# RP2040_MCU.net
KiCad netlist of a schematic drawn in Altium Designer
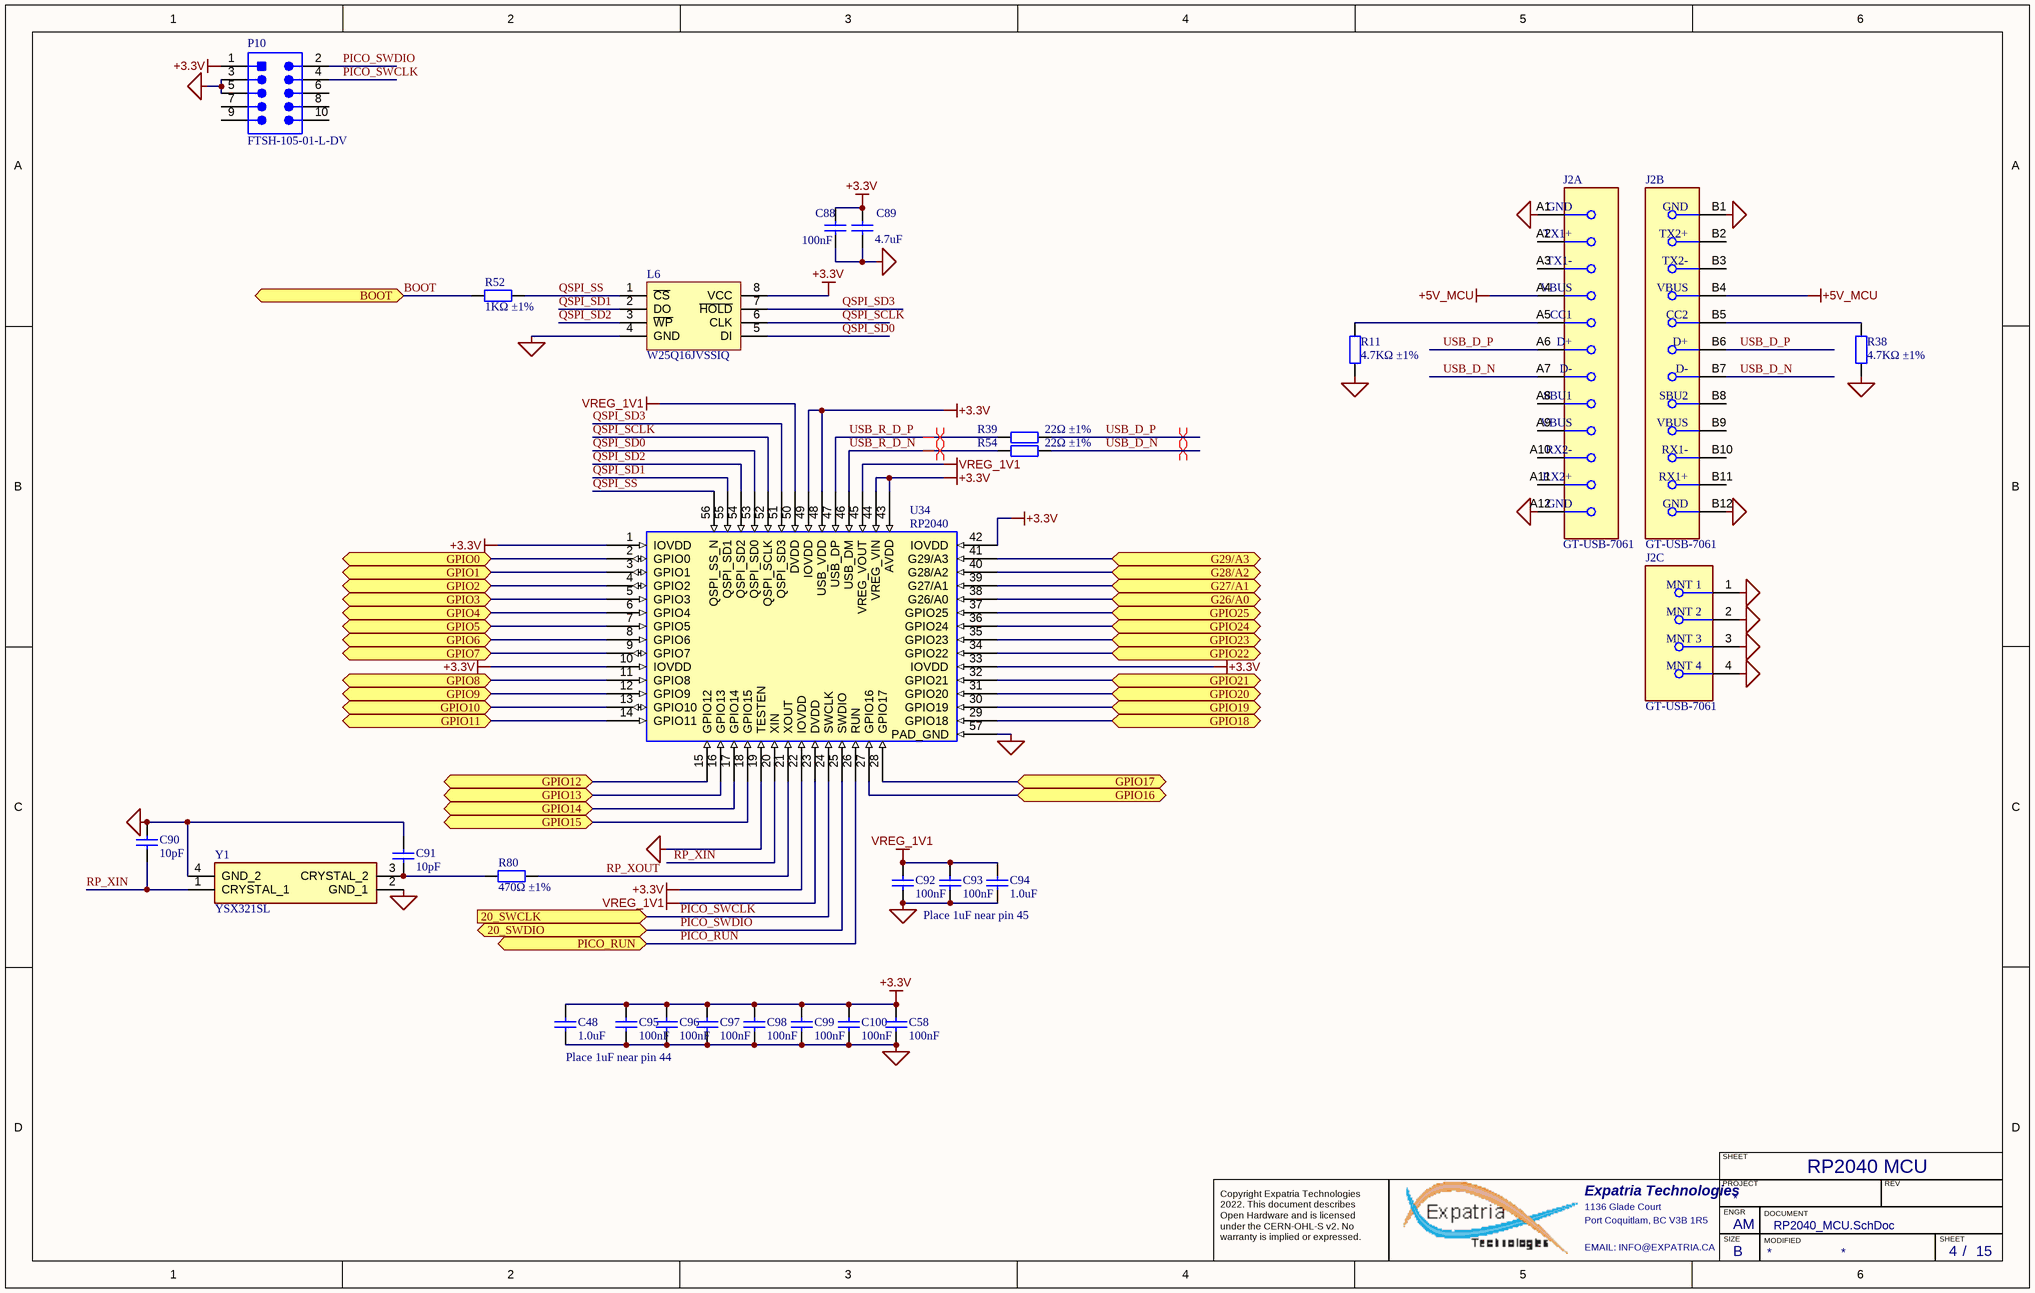
[diagram p0: RP2040_MCU.SchDoc]

(export (version "E")
  (design (tool "Eeschema 10.0.6"))
  (components
    (comp (ref "C48")
      (value "1.0uF")
      (footprint "0402_C")
      (description "Chip capacitor")
      (fields
        (field (name "MANUFACTURER") "Samsung Electro-Mechanics")
        (field (name "PARTNUMBER") "CL05A105KA5NQNC")
      )
      (libsource (lib "Cap") (part "0402 1.0uF (105) 10% 25V"))
    )
    (comp (ref "C58")
      (value "100nF")
      (footprint "0402_C")
      (description "Chip capacitors")
      (fields
        (field (name "MANUFACTURER") "Samsung Electro-Mechanics")
        (field (name "PARTNUMBER") "CL05B104KO5NNNC")
      )
      (libsource (lib "Cap") (part "0402 100nF (104) 10% 16V"))
    )
    (comp (ref "C88")
      (value "100nF")
      (footprint "0402_C")
      (description "Chip capacitors")
      (fields
        (field (name "MANUFACTURER") "Samsung Electro-Mechanics")
        (field (name "PARTNUMBER") "CL05B104KO5NNNC")
      )
      (libsource (lib "Cap") (part "0402 100nF (104) 10% 16V"))
    )
    (comp (ref "C89")
      (value "4.7uF")
      (footprint "0402_C")
      (description "Chip capacitor")
      (fields
        (field (name "MANUFACTURER") "Samsung Electro-Mechanics")
        (field (name "PARTNUMBER") "CL05A475MP5NRNC")
      )
      (libsource (lib "Cap") (part "0402 4.7uF (475) 20% 10V"))
    )
    (comp (ref "C90")
      (value "10pF")
      (footprint "0402_C")
      (description "Chip capacitors")
      (fields
        (field (name "MANUFACTURER") "Samsung Electro-Mechanics")
        (field (name "PARTNUMBER") "CL05C100JB5NNNC")
      )
      (libsource (lib "Cap") (part "0402 10pF (100) 5% 50V"))
    )
    (comp (ref "C91")
      (value "10pF")
      (footprint "0402_C")
      (description "Chip capacitors")
      (fields
        (field (name "MANUFACTURER") "Samsung Electro-Mechanics")
        (field (name "PARTNUMBER") "CL05C100JB5NNNC")
      )
      (libsource (lib "Cap") (part "0402 10pF (100) 5% 50V"))
    )
    (comp (ref "C92")
      (value "100nF")
      (footprint "0402_C")
      (description "Chip capacitors")
      (fields
        (field (name "MANUFACTURER") "Samsung Electro-Mechanics")
        (field (name "PARTNUMBER") "CL05B104KO5NNNC")
      )
      (libsource (lib "Cap") (part "0402 100nF (104) 10% 16V"))
    )
    (comp (ref "C93")
      (value "100nF")
      (footprint "0402_C")
      (description "Chip capacitors")
      (fields
        (field (name "MANUFACTURER") "Samsung Electro-Mechanics")
        (field (name "PARTNUMBER") "CL05B104KO5NNNC")
      )
      (libsource (lib "Cap") (part "0402 100nF (104) 10% 16V"))
    )
    (comp (ref "C94")
      (value "1.0uF")
      (footprint "0402_C")
      (description "Chip capacitor")
      (fields
        (field (name "MANUFACTURER") "Samsung Electro-Mechanics")
        (field (name "PARTNUMBER") "CL05A105KA5NQNC")
      )
      (libsource (lib "Cap") (part "0402 1.0uF (105) 10% 25V"))
    )
    (comp (ref "C95")
      (value "100nF")
      (footprint "0402_C")
      (description "Chip capacitors")
      (fields
        (field (name "MANUFACTURER") "Samsung Electro-Mechanics")
        (field (name "PARTNUMBER") "CL05B104KO5NNNC")
      )
      (libsource (lib "Cap") (part "0402 100nF (104) 10% 16V"))
    )
    (comp (ref "C96")
      (value "100nF")
      (footprint "0402_C")
      (description "Chip capacitors")
      (fields
        (field (name "MANUFACTURER") "Samsung Electro-Mechanics")
        (field (name "PARTNUMBER") "CL05B104KO5NNNC")
      )
      (libsource (lib "Cap") (part "0402 100nF (104) 10% 16V"))
    )
    (comp (ref "C97")
      (value "100nF")
      (footprint "0402_C")
      (description "Chip capacitors")
      (fields
        (field (name "MANUFACTURER") "Samsung Electro-Mechanics")
        (field (name "PARTNUMBER") "CL05B104KO5NNNC")
      )
      (libsource (lib "Cap") (part "0402 100nF (104) 10% 16V"))
    )
    (comp (ref "C98")
      (value "100nF")
      (footprint "0402_C")
      (description "Chip capacitors")
      (fields
        (field (name "MANUFACTURER") "Samsung Electro-Mechanics")
        (field (name "PARTNUMBER") "CL05B104KO5NNNC")
      )
      (libsource (lib "Cap") (part "0402 100nF (104) 10% 16V"))
    )
    (comp (ref "C99")
      (value "100nF")
      (footprint "0402_C")
      (description "Chip capacitors")
      (fields
        (field (name "MANUFACTURER") "Samsung Electro-Mechanics")
        (field (name "PARTNUMBER") "CL05B104KO5NNNC")
      )
      (libsource (lib "Cap") (part "0402 100nF (104) 10% 16V"))
    )
    (comp (ref "C100")
      (value "100nF")
      (footprint "0402_C")
      (description "Chip capacitors")
      (fields
        (field (name "MANUFACTURER") "Samsung Electro-Mechanics")
        (field (name "PARTNUMBER") "CL05B104KO5NNNC")
      )
      (libsource (lib "Cap") (part "0402 100nF (104) 10% 16V"))
    )
    (comp (ref "J2")
      (value "GT-USB-7061")
      (footprint "USB-C-SMD_GT-USB-7061")
      (description "CONN RCP USB3.1 TYPEC 24P SMD VERT")
      (fields (field (name "MANUFACTURER") "G-Switch"))
      (libsource (lib "I2C_Jog_Controller") (part "USBC-GT-USB-7061"))
    )
    (comp (ref "L6")
      (value "W25Q16JVSSIQ")
      (footprint "SOIC-8_208mil")
      (description "Flash ROM")
      (libsource (lib "IC") (part "W25Q128JVSIQTR_[C97521]"))
    )
    (comp (ref "P10")
      (value "FTSH-105-01-L-DV")
      (footprint "SMTC-FTSH-105-01-L-DV_V")
      (description "Male Header, Pitch 1.27 mm, 2 x 5 Position, Height 5.96 mm, -55 to 125 degC, RoHS, Bulk")
      (fields (field (name "MANUFACTURER") "Samtec"))
      (libsource (lib "Altium Content Vault") (part "CN-2P-M-R10"))
    )
    (comp (ref "R11")
      (value "4.7KΩ ±1%")
      (footprint "0402_R")
      (description "Chip resistor")
      (fields (field (name "MANUFACTURER") "Uniroyal Elec") (field (name "PARTNUMBER") "0402WGF4701TCE"))
      (libsource (lib "RES") (part "0402 4.7K (4701) 1%"))
    )
    (comp (ref "R38")
      (value "4.7KΩ ±1%")
      (footprint "0402_R")
      (description "Chip resistor")
      (fields (field (name "MANUFACTURER") "Uniroyal Elec") (field (name "PARTNUMBER") "0402WGF4701TCE"))
      (libsource (lib "") (part "0402 4.7K (4701) 1%_1"))
    )
    (comp (ref "R39")
      (value "22Ω ±1%")
      (footprint "0402_R")
      (description "Chip resistor")
      (fields (field (name "MANUFACTURER") "Uniroyal Elec") (field (name "PARTNUMBER") "0402WGF220JTCE"))
      (libsource (lib "RES") (part "0402 22R (22R0) 1%"))
    )
    (comp (ref "R52")
      (value "1KΩ ±1%")
      (footprint "0402_R")
      (description "Chip resistor")
      (fields (field (name "MANUFACTURER") "Uniroyal Elec") (field (name "PARTNUMBER") "0402WGF1001TCE"))
      (libsource (lib "RES") (part "0402 1K (1001) 1%"))
    )
    (comp (ref "R54")
      (value "22Ω ±1%")
      (footprint "0402_R")
      (description "Chip resistor")
      (fields (field (name "MANUFACTURER") "Uniroyal Elec") (field (name "PARTNUMBER") "0402WGF220JTCE"))
      (libsource (lib "RES") (part "0402 22R (22R0) 1%"))
    )
    (comp (ref "R80")
      (value "470Ω ±1%")
      (footprint "0402_R")
      (description "Chip resistor")
      (fields (field (name "MANUFACTURER") "Uniroyal Elec") (field (name "PARTNUMBER") "0402WGF4700TCE"))
      (libsource (lib "RES") (part "0402 470R (4700) 1%"))
    )
    (comp (ref "U34")
      (value "RP2040")
      (footprint "RP2040")
      (description "RP2040 First MCU from RPI")
      (libsource (lib "Universal_CNC_Breakout") (part "RP2040"))
    )
    (comp (ref "Y1")
      (value "YSX321SL")
      (footprint "YSX321SL")
      (description "Crystal or Oscillator")
      (libsource (lib "*") (part "YSX321SL"))
    )
  )
  (nets
    (net (code "1") (name "+3.3V") (class "Default")
      (node (ref "C100") (pin "2") (pinfunction "2_2") (pintype "passive"))
      (node (ref "C48") (pin "2") (pinfunction "2_2") (pintype "passive"))
      (node (ref "C58") (pin "2") (pinfunction "2_2") (pintype "passive"))
      (node (ref "C88") (pin "2") (pinfunction "2_2") (pintype "passive"))
      (node (ref "C89") (pin "2") (pinfunction "2_2") (pintype "passive"))
      (node (ref "C95") (pin "2") (pinfunction "2_2") (pintype "passive"))
      (node (ref "C96") (pin "2") (pinfunction "2_2") (pintype "passive"))
      (node (ref "C97") (pin "2") (pinfunction "2_2") (pintype "passive"))
      (node (ref "C98") (pin "2") (pinfunction "2_2") (pintype "passive"))
      (node (ref "C99") (pin "2") (pinfunction "2_2") (pintype "passive"))
      (node (ref "L6") (pin "8") (pinfunction "VCC_8") (pintype "passive"))
      (node (ref "P10") (pin "1") (pinfunction "1_1") (pintype "passive"))
      (node (ref "U34") (pin "1") (pinfunction "IOVDD_1") (pintype "input"))
      (node (ref "U34") (pin "10") (pinfunction "IOVDD_10") (pintype "input"))
      (node (ref "U34") (pin "22") (pinfunction "IOVDD_22") (pintype "input"))
      (node (ref "U34") (pin "33") (pinfunction "IOVDD_33") (pintype "input"))
      (node (ref "U34") (pin "42") (pinfunction "IOVDD_42") (pintype "input"))
      (node (ref "U34") (pin "43") (pinfunction "AVDD_43") (pintype "input"))
      (node (ref "U34") (pin "44") (pinfunction "VREG_VIN_44") (pintype "input"))
      (node (ref "U34") (pin "48") (pinfunction "USB_VDD_48") (pintype "input"))
      (node (ref "U34") (pin "49") (pinfunction "IOVDD_49") (pintype "input"))
    )
    (net (code "2") (name "+5V_MCU") (class "Default")
      (node (ref "J2") (pin "A4") (pinfunction "VBUS_A4") (pintype "passive"))
      (node (ref "J2") (pin "B4") (pinfunction "VBUS_B4") (pintype "passive"))
    )
    (net (code "3") (name "/BOOT") (class "Default")
      (node (ref "R52") (pin "1") (pinfunction "1_1") (pintype "passive"))
    )
    (net (code "4") (name "/G26{slash}A0") (class "Default")
      (node (ref "U34") (pin "38") (pinfunction "G26/A0_38") (pintype "input"))
    )
    (net (code "5") (name "/G27{slash}A1") (class "Default")
      (node (ref "U34") (pin "39") (pinfunction "G27/A1_39") (pintype "input"))
    )
    (net (code "6") (name "/G28{slash}A2") (class "Default")
      (node (ref "U34") (pin "40") (pinfunction "G28/A2_40") (pintype "input"))
    )
    (net (code "7") (name "/G29{slash}A3") (class "Default")
      (node (ref "U34") (pin "41") (pinfunction "G29/A3_41") (pintype "input"))
    )
    (net (code "8") (name "/GPIO0") (class "Default")
      (node (ref "U34") (pin "2") (pinfunction "GPIO0_2") (pintype "bidirectional"))
    )
    (net (code "9") (name "/GPIO1") (class "Default")
      (node (ref "U34") (pin "3") (pinfunction "GPIO1_3") (pintype "bidirectional"))
    )
    (net (code "10") (name "/GPIO2") (class "Default")
      (node (ref "U34") (pin "4") (pinfunction "GPIO2_4") (pintype "bidirectional"))
    )
    (net (code "11") (name "/GPIO3") (class "Default")
      (node (ref "U34") (pin "5") (pinfunction "GPIO3_5") (pintype "input"))
    )
    (net (code "12") (name "/GPIO4") (class "Default")
      (node (ref "U34") (pin "6") (pinfunction "GPIO4_6") (pintype "input"))
    )
    (net (code "13") (name "/GPIO5") (class "Default")
      (node (ref "U34") (pin "7") (pinfunction "GPIO5_7") (pintype "input"))
    )
    (net (code "14") (name "/GPIO6") (class "Default")
      (node (ref "U34") (pin "8") (pinfunction "GPIO6_8") (pintype "input"))
    )
    (net (code "15") (name "/GPIO7") (class "Default")
      (node (ref "U34") (pin "9") (pinfunction "GPIO7_9") (pintype "bidirectional"))
    )
    (net (code "16") (name "/GPIO8") (class "Default")
      (node (ref "U34") (pin "11") (pinfunction "GPIO8_11") (pintype "input"))
    )
    (net (code "17") (name "/GPIO9") (class "Default")
      (node (ref "U34") (pin "12") (pinfunction "GPIO9_12") (pintype "input"))
    )
    (net (code "18") (name "/GPIO10") (class "Default")
      (node (ref "U34") (pin "13") (pinfunction "GPIO10_13") (pintype "bidirectional"))
    )
    (net (code "19") (name "/GPIO11") (class "Default")
      (node (ref "U34") (pin "14") (pinfunction "GPIO11_14") (pintype "input"))
    )
    (net (code "20") (name "/GPIO12") (class "Default")
      (node (ref "U34") (pin "15") (pinfunction "GPIO12_15") (pintype "input"))
    )
    (net (code "21") (name "/GPIO13") (class "Default")
      (node (ref "U34") (pin "16") (pinfunction "GPIO13_16") (pintype "input"))
    )
    (net (code "22") (name "/GPIO14") (class "Default")
      (node (ref "U34") (pin "17") (pinfunction "GPIO14_17") (pintype "input"))
    )
    (net (code "23") (name "/GPIO15") (class "Default")
      (node (ref "U34") (pin "18") (pinfunction "GPIO15_18") (pintype "input"))
    )
    (net (code "24") (name "/GPIO16") (class "Default")
      (node (ref "U34") (pin "27") (pinfunction "GPIO16_27") (pintype "input"))
    )
    (net (code "25") (name "/GPIO17") (class "Default")
      (node (ref "U34") (pin "28") (pinfunction "GPIO17_28") (pintype "input"))
    )
    (net (code "26") (name "/GPIO18") (class "Default")
      (node (ref "U34") (pin "29") (pinfunction "GPIO18_29") (pintype "input"))
    )
    (net (code "27") (name "/GPIO19") (class "Default")
      (node (ref "U34") (pin "30") (pinfunction "GPIO19_30") (pintype "input"))
    )
    (net (code "28") (name "/GPIO20") (class "Default")
      (node (ref "U34") (pin "31") (pinfunction "GPIO20_31") (pintype "input"))
    )
    (net (code "29") (name "/GPIO21") (class "Default")
      (node (ref "U34") (pin "32") (pinfunction "GPIO21_32") (pintype "input"))
    )
    (net (code "30") (name "/GPIO22") (class "Default")
      (node (ref "U34") (pin "34") (pinfunction "GPIO22_34") (pintype "input"))
    )
    (net (code "31") (name "/GPIO23") (class "Default")
      (node (ref "U34") (pin "35") (pinfunction "GPIO23_35") (pintype "input"))
    )
    (net (code "32") (name "/GPIO24") (class "Default")
      (node (ref "U34") (pin "36") (pinfunction "GPIO24_36") (pintype "input"))
    )
    (net (code "33") (name "/GPIO25") (class "Default")
      (node (ref "U34") (pin "37") (pinfunction "GPIO25_37") (pintype "input"))
    )
    (net (code "34") (name "/PICO_RUN") (class "Default")
      (node (ref "U34") (pin "26") (pinfunction "RUN_26") (pintype "input"))
    )
    (net (code "35") (name "/PICO_SWCLK") (class "Default")
      (node (ref "P10") (pin "4") (pinfunction "4_4") (pintype "passive"))
      (node (ref "U34") (pin "24") (pinfunction "SWCLK_24") (pintype "input"))
    )
    (net (code "36") (name "/PICO_SWDIO") (class "Default")
      (node (ref "P10") (pin "2") (pinfunction "2_2") (pintype "passive"))
      (node (ref "U34") (pin "25") (pinfunction "SWDIO_25") (pintype "input"))
    )
    (net (code "37") (name "/QSPI_SCLK") (class "Default")
      (node (ref "L6") (pin "6") (pinfunction "CLK_6") (pintype "passive"))
      (node (ref "U34") (pin "52") (pinfunction "QSPI_SCLK_52") (pintype "input"))
    )
    (net (code "38") (name "/QSPI_SD0") (class "Default")
      (node (ref "L6") (pin "5") (pinfunction "DI_5") (pintype "passive"))
      (node (ref "U34") (pin "53") (pinfunction "QSPI_SD0_53") (pintype "input"))
    )
    (net (code "39") (name "/QSPI_SD1") (class "Default")
      (node (ref "L6") (pin "2") (pinfunction "DO_2") (pintype "passive"))
      (node (ref "U34") (pin "55") (pinfunction "QSPI_SD1_55") (pintype "input"))
    )
    (net (code "40") (name "/QSPI_SD2") (class "Default")
      (node (ref "L6") (pin "3") (pinfunction "~{WP}_3") (pintype "passive"))
      (node (ref "U34") (pin "54") (pinfunction "QSPI_SD2_54") (pintype "input"))
    )
    (net (code "41") (name "/QSPI_SD3") (class "Default")
      (node (ref "L6") (pin "7") (pinfunction "~{HOLD}_7") (pintype "passive"))
      (node (ref "U34") (pin "51") (pinfunction "QSPI_SD3_51") (pintype "input"))
    )
    (net (code "42") (name "/QSPI_SS") (class "Default")
      (node (ref "L6") (pin "1") (pinfunction "~{CS}_1") (pintype "passive"))
      (node (ref "R52") (pin "2") (pinfunction "2_2") (pintype "passive"))
      (node (ref "U34") (pin "56") (pinfunction "QSPI_SS_N_56") (pintype "input"))
    )
    (net (code "43") (name "/RP_XIN") (class "Default")
      (node (ref "C90") (pin "1") (pinfunction "1_1") (pintype "passive"))
      (node (ref "U34") (pin "20") (pinfunction "XIN_20") (pintype "input"))
      (node (ref "Y1") (pin "1") (pinfunction "CRYSTAL_1_1") (pintype "passive"))
    )
    (net (code "44") (name "/RP_XOUT") (class "Default")
      (node (ref "R80") (pin "2") (pinfunction "2_2") (pintype "passive"))
      (node (ref "U34") (pin "21") (pinfunction "XOUT_21") (pintype "input"))
    )
    (net (code "45") (name "/USB_D_N") (class "Default")
      (node (ref "J2") (pin "A7") (pinfunction "D-_A7") (pintype "passive"))
      (node (ref "J2") (pin "B7") (pinfunction "D-_B7") (pintype "passive"))
      (node (ref "R54") (pin "1") (pinfunction "1_1") (pintype "passive"))
    )
    (net (code "46") (name "/USB_D_P") (class "Default")
      (node (ref "J2") (pin "A6") (pinfunction "D+_A6") (pintype "passive"))
      (node (ref "J2") (pin "B6") (pinfunction "D+_B6") (pintype "passive"))
      (node (ref "R39") (pin "1") (pinfunction "1_1") (pintype "passive"))
    )
    (net (code "47") (name "/USB_R_D_N") (class "Default")
      (node (ref "R54") (pin "2") (pinfunction "2_2") (pintype "passive"))
      (node (ref "U34") (pin "46") (pinfunction "USB_DM_46") (pintype "input"))
    )
    (net (code "48") (name "/USB_R_D_P") (class "Default")
      (node (ref "R39") (pin "2") (pinfunction "2_2") (pintype "passive"))
      (node (ref "U34") (pin "47") (pinfunction "USB_DP_47") (pintype "input"))
    )
    (net (code "49") (name "GND_CONN") (class "Default")
      (node (ref "J2") (pin "1") (pinfunction "MNT_1_1") (pintype "passive"))
      (node (ref "J2") (pin "2") (pinfunction "MNT_2_2") (pintype "passive"))
      (node (ref "J2") (pin "3") (pinfunction "MNT_3_3") (pintype "passive"))
      (node (ref "J2") (pin "4") (pinfunction "MNT_4_4") (pintype "passive"))
    )
    (net (code "50") (name "MCU_GND") (class "Default")
      (node (ref "C100") (pin "1") (pinfunction "1_1") (pintype "passive"))
      (node (ref "C48") (pin "1") (pinfunction "1_1") (pintype "passive"))
      (node (ref "C58") (pin "1") (pinfunction "1_1") (pintype "passive"))
      (node (ref "C88") (pin "1") (pinfunction "1_1") (pintype "passive"))
      (node (ref "C89") (pin "1") (pinfunction "1_1") (pintype "passive"))
      (node (ref "C90") (pin "2") (pinfunction "2_2") (pintype "passive"))
      (node (ref "C91") (pin "2") (pinfunction "2_2") (pintype "passive"))
      (node (ref "C92") (pin "1") (pinfunction "1_1") (pintype "passive"))
      (node (ref "C93") (pin "1") (pinfunction "1_1") (pintype "passive"))
      (node (ref "C94") (pin "1") (pinfunction "1_1") (pintype "passive"))
      (node (ref "C95") (pin "1") (pinfunction "1_1") (pintype "passive"))
      (node (ref "C96") (pin "1") (pinfunction "1_1") (pintype "passive"))
      (node (ref "C97") (pin "1") (pinfunction "1_1") (pintype "passive"))
      (node (ref "C98") (pin "1") (pinfunction "1_1") (pintype "passive"))
      (node (ref "C99") (pin "1") (pinfunction "1_1") (pintype "passive"))
      (node (ref "J2") (pin "A1") (pinfunction "GND_A1") (pintype "passive"))
      (node (ref "J2") (pin "A12") (pinfunction "GND_A12") (pintype "passive"))
      (node (ref "J2") (pin "B1") (pinfunction "GND_B1") (pintype "passive"))
      (node (ref "J2") (pin "B12") (pinfunction "GND_B12") (pintype "passive"))
      (node (ref "L6") (pin "4") (pinfunction "GND_4") (pintype "passive"))
      (node (ref "P10") (pin "3") (pinfunction "3_3") (pintype "passive"))
      (node (ref "P10") (pin "5") (pinfunction "5_5") (pintype "passive"))
      (node (ref "R11") (pin "2") (pinfunction "2_2") (pintype "passive"))
      (node (ref "R38") (pin "2") (pinfunction "2_2") (pintype "passive"))
      (node (ref "U34") (pin "19") (pinfunction "TESTEN_19") (pintype "input"))
      (node (ref "U34") (pin "57") (pinfunction "PAD_GND_57") (pintype "input"))
      (node (ref "Y1") (pin "2") (pinfunction "GND_1_2") (pintype "passive"))
      (node (ref "Y1") (pin "4") (pinfunction "GND_2_4") (pintype "passive"))
    )
    (net (code "51") (name "Net-(J2A-CC1)") (class "Default")
      (node (ref "J2") (pin "A5") (pinfunction "CC1_A5") (pintype "passive"))
      (node (ref "R11") (pin "1") (pinfunction "1_1") (pintype "passive"))
    )
    (net (code "52") (name "Net-(J2B-CC2)") (class "Default")
      (node (ref "J2") (pin "B5") (pinfunction "CC2_B5") (pintype "passive"))
      (node (ref "R38") (pin "1") (pinfunction "1_1") (pintype "passive"))
    )
    (net (code "53") (name "Net-(Y1-CRYSTAL_2)") (class "Default")
      (node (ref "C91") (pin "1") (pinfunction "1_1") (pintype "passive"))
      (node (ref "R80") (pin "1") (pinfunction "1_1") (pintype "passive"))
      (node (ref "Y1") (pin "3") (pinfunction "CRYSTAL_2_3") (pintype "passive"))
    )
    (net (code "54") (name "VREG_1V1") (class "Default")
      (node (ref "C92") (pin "2") (pinfunction "2_2") (pintype "passive"))
      (node (ref "C93") (pin "2") (pinfunction "2_2") (pintype "passive"))
      (node (ref "C94") (pin "2") (pinfunction "2_2") (pintype "passive"))
      (node (ref "U34") (pin "23") (pinfunction "DVDD_23") (pintype "input"))
      (node (ref "U34") (pin "45") (pinfunction "VREG_VOUT_45") (pintype "input"))
      (node (ref "U34") (pin "50") (pinfunction "DVDD_50") (pintype "input"))
    )
    (net (code "55") (name "unconnected-(J2A-RX2+-PadA11)") (class "Default")
      (node (ref "J2") (pin "A11") (pinfunction "RX2+_A11") (pintype "passive"))
    )
    (net (code "56") (name "unconnected-(J2A-RX2--PadA10)") (class "Default")
      (node (ref "J2") (pin "A10") (pinfunction "RX2-_A10") (pintype "passive"))
    )
    (net (code "57") (name "unconnected-(J2A-SBU1-PadA8)") (class "Default")
      (node (ref "J2") (pin "A8") (pinfunction "SBU1_A8") (pintype "passive"))
    )
    (net (code "58") (name "unconnected-(J2A-TX1+-PadA2)") (class "Default")
      (node (ref "J2") (pin "A2") (pinfunction "TX1+_A2") (pintype "passive"))
    )
    (net (code "59") (name "unconnected-(J2A-TX1--PadA3)") (class "Default")
      (node (ref "J2") (pin "A3") (pinfunction "TX1-_A3") (pintype "passive"))
    )
    (net (code "60") (name "unconnected-(J2A-VBUS-PadA9)") (class "Default")
      (node (ref "J2") (pin "A9") (pinfunction "VBUS_A9") (pintype "passive"))
    )
    (net (code "61") (name "unconnected-(J2B-RX1+-PadB11)") (class "Default")
      (node (ref "J2") (pin "B11") (pinfunction "RX1+_B11") (pintype "passive"))
    )
    (net (code "62") (name "unconnected-(J2B-RX1--PadB10)") (class "Default")
      (node (ref "J2") (pin "B10") (pinfunction "RX1-_B10") (pintype "passive"))
    )
    (net (code "63") (name "unconnected-(J2B-SBU2-PadB8)") (class "Default")
      (node (ref "J2") (pin "B8") (pinfunction "SBU2_B8") (pintype "passive"))
    )
    (net (code "64") (name "unconnected-(J2B-TX2+-PadB2)") (class "Default")
      (node (ref "J2") (pin "B2") (pinfunction "TX2+_B2") (pintype "passive"))
    )
    (net (code "65") (name "unconnected-(J2B-TX2--PadB3)") (class "Default")
      (node (ref "J2") (pin "B3") (pinfunction "TX2-_B3") (pintype "passive"))
    )
    (net (code "66") (name "unconnected-(J2B-VBUS-PadB9)") (class "Default")
      (node (ref "J2") (pin "B9") (pinfunction "VBUS_B9") (pintype "passive"))
    )
    (net (code "67") (name "unconnected-(P10-Pad6)") (class "Default")
      (node (ref "P10") (pin "6") (pinfunction "6_6") (pintype "passive"))
    )
    (net (code "68") (name "unconnected-(P10-Pad7)") (class "Default")
      (node (ref "P10") (pin "7") (pinfunction "7_7") (pintype "passive"))
    )
    (net (code "69") (name "unconnected-(P10-Pad8)") (class "Default")
      (node (ref "P10") (pin "8") (pinfunction "8_8") (pintype "passive"))
    )
    (net (code "70") (name "unconnected-(P10-Pad9)") (class "Default")
      (node (ref "P10") (pin "9") (pinfunction "9_9") (pintype "passive"))
    )
    (net (code "71") (name "unconnected-(P10-Pad10)") (class "Default")
      (node (ref "P10") (pin "10") (pinfunction "10_10") (pintype "passive"))
    )
  )
)
